# GPIO_Button_Grove_MOSFET_LED.net
KiCad netlist of a schematic drawn in EasyEDA Pro
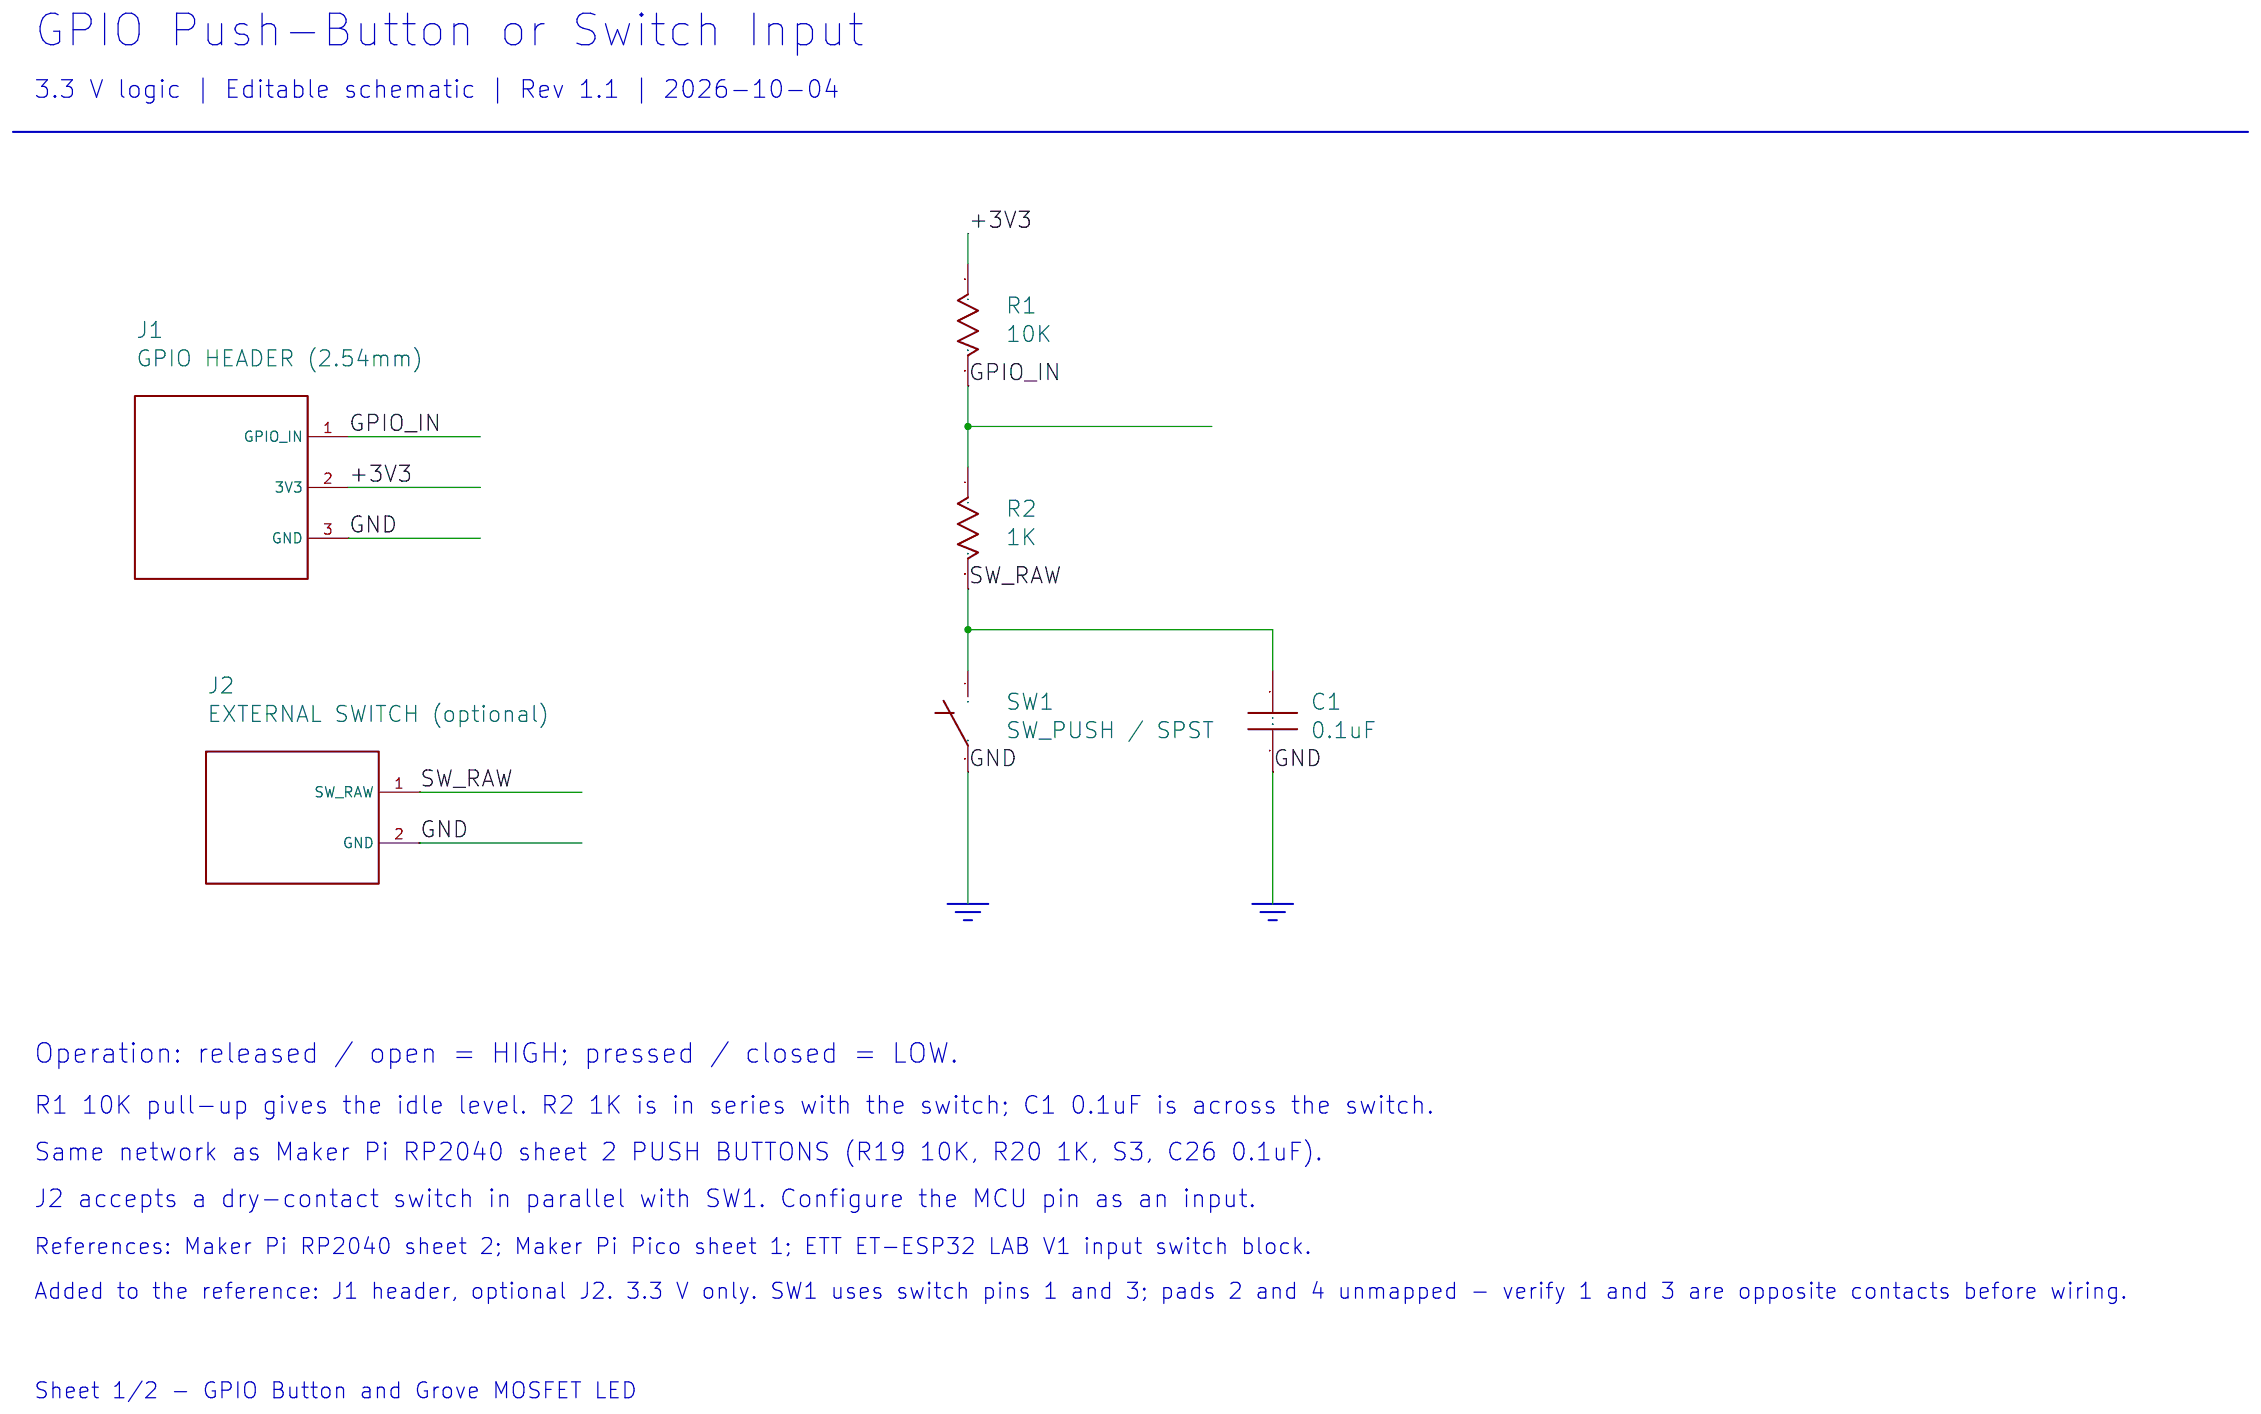
[diagram p0: GPIO_Push-Button_or_Switch_Input]
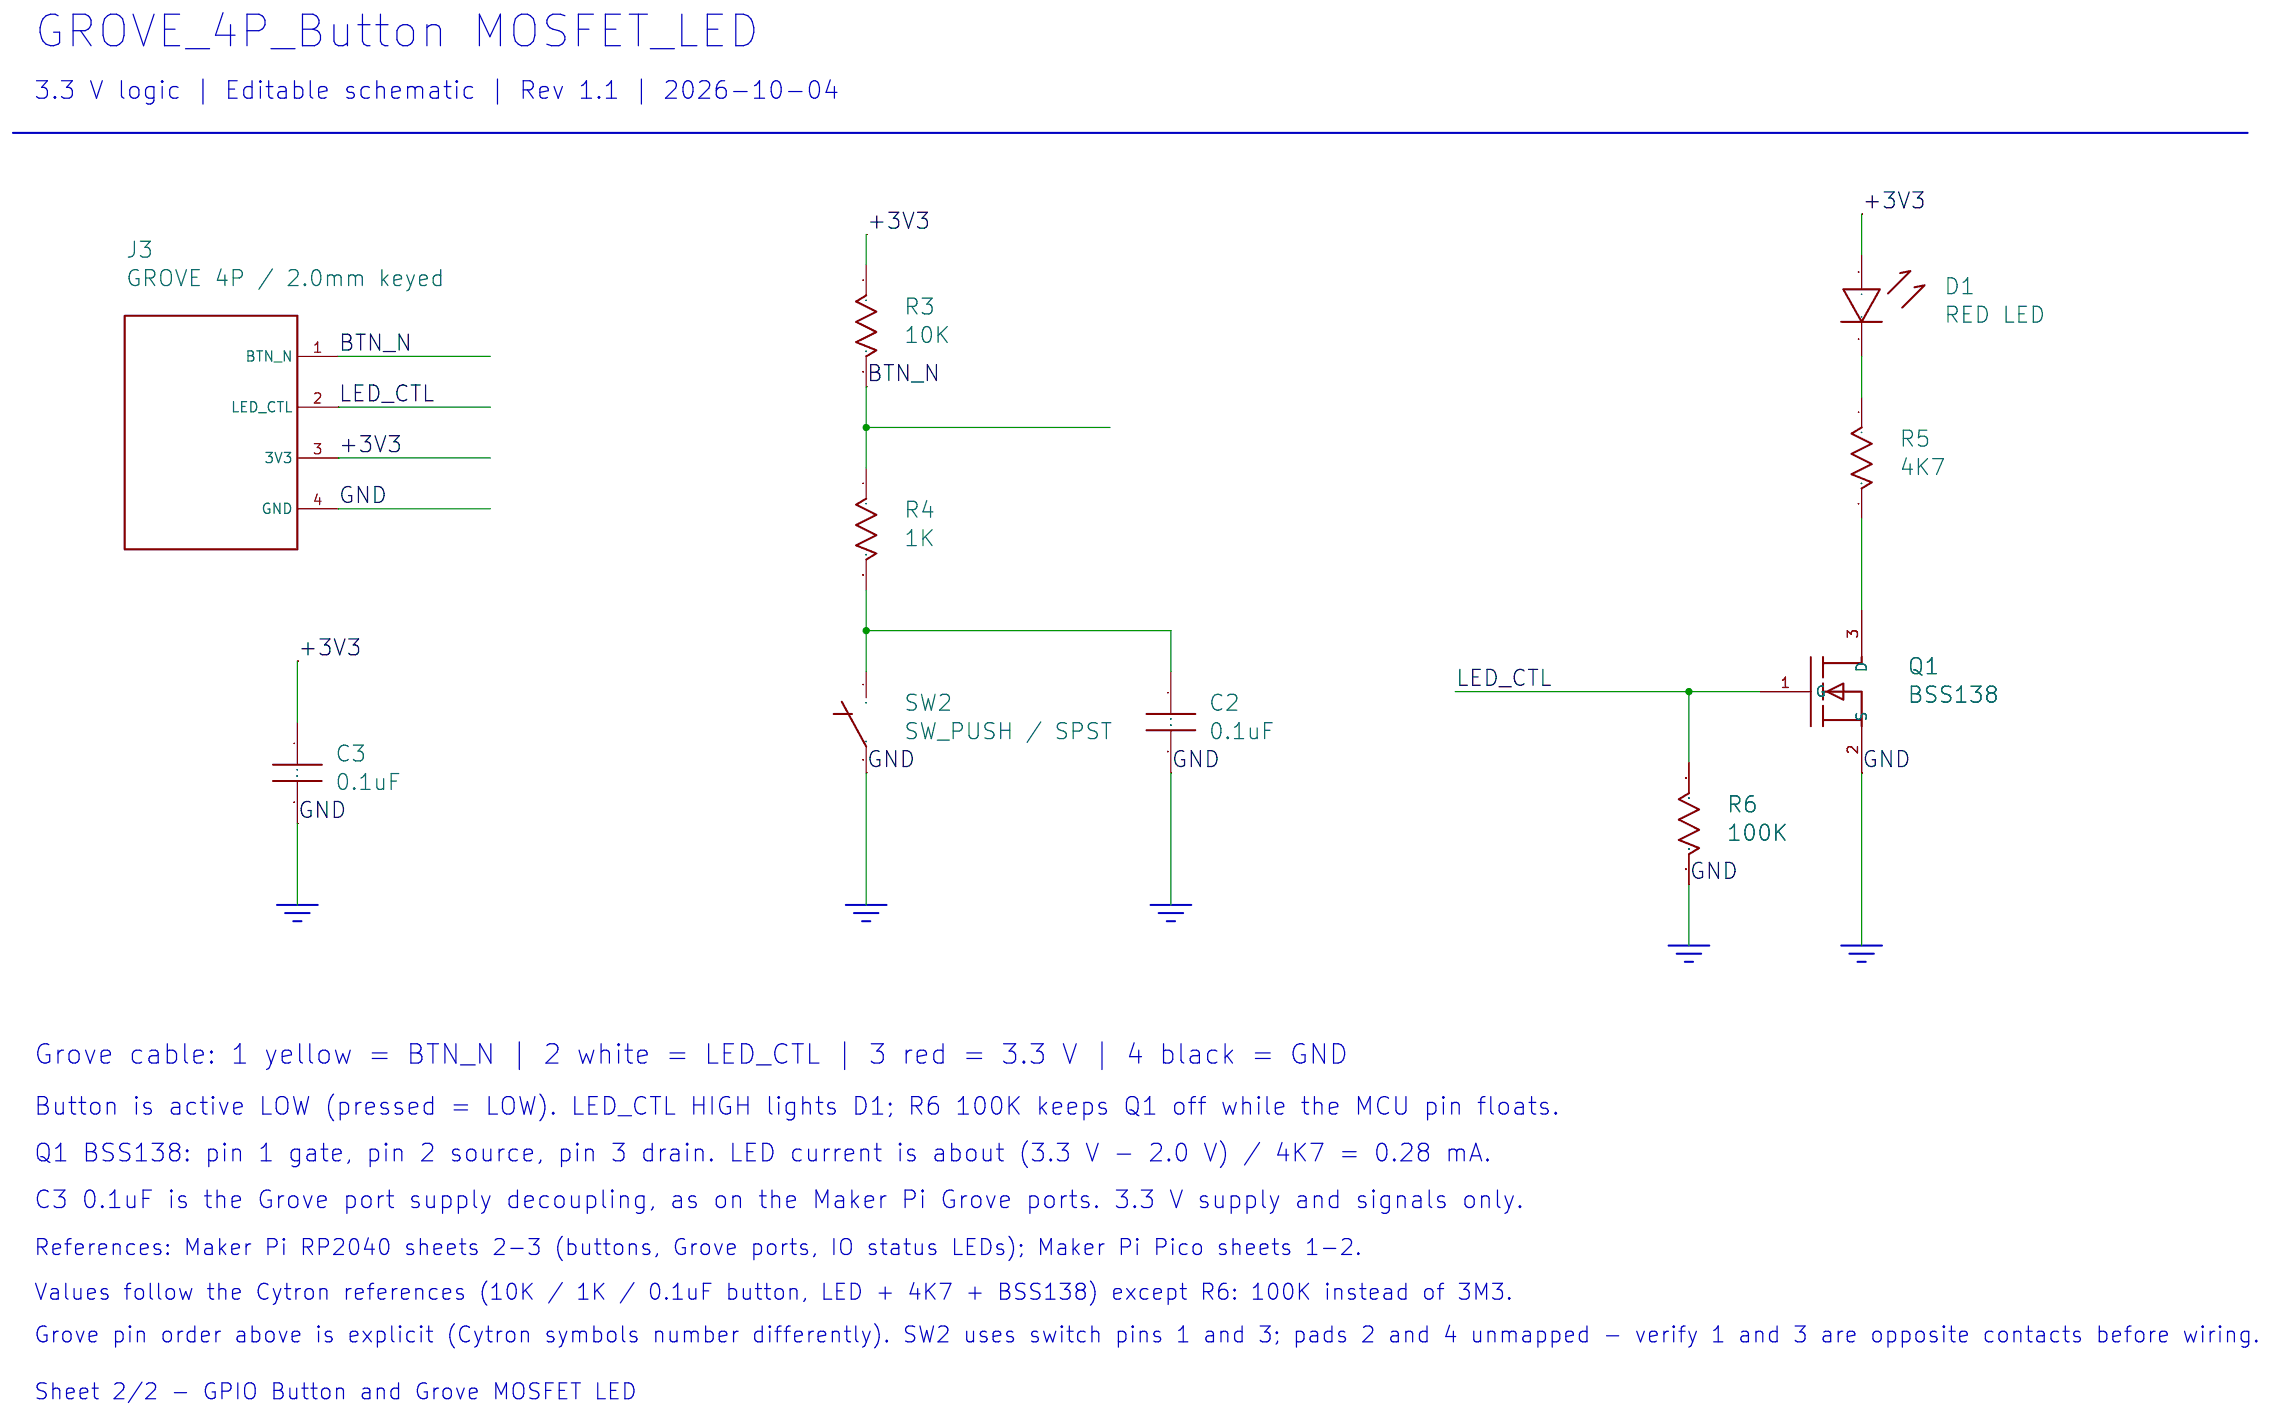
[diagram p1: GROVE_4P_Button_MOSFET_LED]

(export (version "E")
  (design (tool "Eeschema 10.0.6"))
  (components
    (comp (ref "C1")
      (value "0.1uF")
      (footprint "easyedapro:C0603")
      (libsource (lib "easyedapro") (part "0.1uF"))
    )
    (comp (ref "J1")
      (value "GPIO HEADER (2.54mm)")
      (libsource (lib "easyedapro") (part "GPIO HEADER (2.54mm)"))
    )
    (comp (ref "J2")
      (value "EXTERNAL SWITCH (optional)")
      (libsource (lib "easyedapro") (part "EXTERNAL SWITCH (optional)"))
    )
    (comp (ref "R1") (value "10K") (footprint "easyedapro:R0603") (libsource (lib "easyedapro") (part "10K")))
    (comp (ref "R2") (value "1K") (footprint "easyedapro:R0603") (libsource (lib "easyedapro") (part "1K")))
    (comp (ref "SW1") (value "SW_PUSH / SPST") (libsource (lib "easyedapro") (part "SW_PUSH / SPST")))
    (comp (ref "C2")
      (value "0.1uF")
      (footprint "easyedapro:C0603")
      (libsource (lib "easyedapro") (part "0.1uF"))
    )
    (comp (ref "C3")
      (value "0.1uF")
      (footprint "easyedapro:C0603")
      (libsource (lib "easyedapro") (part "0.1uF"))
    )
    (comp (ref "D1")
      (value "RED LED")
      (footprint "easyedapro:LED0603")
      (libsource (lib "easyedapro") (part "RED LED"))
    )
    (comp (ref "J3")
      (value "GROVE 4P / 2.0mm keyed")
      (libsource (lib "easyedapro") (part "GROVE 4P / 2.0mm keyed"))
    )
    (comp (ref "Q1") (value "BSS138") (libsource (lib "easyedapro") (part "BSS138")))
    (comp (ref "R3") (value "10K") (footprint "easyedapro:R0603") (libsource (lib "easyedapro") (part "10K")))
    (comp (ref "R4") (value "1K") (footprint "easyedapro:R0603") (libsource (lib "easyedapro") (part "1K")))
    (comp (ref "R5") (value "4K7") (footprint "easyedapro:R0603") (libsource (lib "easyedapro") (part "4K7")))
    (comp (ref "R6")
      (value "100K")
      (footprint "easyedapro:R0603")
      (libsource (lib "easyedapro") (part "3M3"))
    )
    (comp (ref "SW2") (value "SW_PUSH / SPST") (libsource (lib "easyedapro") (part "SW_PUSH / SPST")))
  )
  (nets
    (net (code "1") (name "+3V3") (class "Default")
      (node (ref "C3") (pin "1") (pinfunction "1_1") (pintype "unspecified"))
      (node (ref "D1") (pin "2") (pinfunction "A_2") (pintype "unspecified"))
      (node (ref "J1") (pin "2") (pinfunction "3V3_2") (pintype "unspecified"))
      (node (ref "J3") (pin "3") (pinfunction "3V3_3") (pintype "unspecified"))
      (node (ref "R1") (pin "1") (pinfunction "1_1") (pintype "unspecified"))
      (node (ref "R3") (pin "1") (pinfunction "1_1") (pintype "unspecified"))
    )
    (net (code "2") (name "BTN_N") (class "Default")
      (node (ref "J3") (pin "1") (pinfunction "BTN_N_1") (pintype "unspecified"))
      (node (ref "R3") (pin "2") (pinfunction "2_2") (pintype "unspecified"))
      (node (ref "R4") (pin "1") (pinfunction "1_1") (pintype "unspecified"))
    )
    (net (code "3") (name "GND") (class "Default")
      (node (ref "C1") (pin "2") (pinfunction "2_2") (pintype "unspecified"))
      (node (ref "C2") (pin "2") (pinfunction "2_2") (pintype "unspecified"))
      (node (ref "C3") (pin "2") (pinfunction "2_2") (pintype "unspecified"))
      (node (ref "J1") (pin "3") (pinfunction "GND_3") (pintype "unspecified"))
      (node (ref "J2") (pin "2") (pinfunction "GND_2") (pintype "unspecified"))
      (node (ref "J3") (pin "4") (pinfunction "GND_4") (pintype "unspecified"))
      (node (ref "Q1") (pin "2") (pinfunction "S_2") (pintype "unspecified"))
      (node (ref "R6") (pin "2") (pinfunction "2_2") (pintype "unspecified"))
      (node (ref "SW1") (pin "2") (pinfunction "2_2") (pintype "unspecified"))
      (node (ref "SW2") (pin "2") (pinfunction "2_2") (pintype "unspecified"))
    )
    (net (code "4") (name "GPIO_IN") (class "Default")
      (node (ref "J1") (pin "1") (pinfunction "GPIO_IN_1") (pintype "unspecified"))
      (node (ref "R1") (pin "2") (pinfunction "2_2") (pintype "unspecified"))
      (node (ref "R2") (pin "1") (pinfunction "1_1") (pintype "unspecified"))
    )
    (net (code "5") (name "LED_CTL") (class "Default")
      (node (ref "J3") (pin "2") (pinfunction "LED_CTL_2") (pintype "unspecified"))
      (node (ref "Q1") (pin "1") (pinfunction "G_1") (pintype "unspecified"))
      (node (ref "R6") (pin "1") (pinfunction "1_1") (pintype "unspecified"))
    )
    (net (code "6") (name "Net-(C2-Pad1)") (class "Default")
      (node (ref "C2") (pin "1") (pinfunction "1_1") (pintype "unspecified"))
      (node (ref "R4") (pin "2") (pinfunction "2_2") (pintype "unspecified"))
      (node (ref "SW2") (pin "1") (pinfunction "1_1") (pintype "unspecified"))
    )
    (net (code "7") (name "Net-(D1-K)") (class "Default")
      (node (ref "D1") (pin "1") (pinfunction "K_1") (pintype "unspecified"))
      (node (ref "R5") (pin "1") (pinfunction "1_1") (pintype "unspecified"))
    )
    (net (code "8") (name "Net-(Q1-D)") (class "Default")
      (node (ref "Q1") (pin "3") (pinfunction "D_3") (pintype "unspecified"))
      (node (ref "R5") (pin "2") (pinfunction "2_2") (pintype "unspecified"))
    )
    (net (code "9") (name "SW_RAW") (class "Default")
      (node (ref "C1") (pin "1") (pinfunction "1_1") (pintype "unspecified"))
      (node (ref "J2") (pin "1") (pinfunction "SW_RAW_1") (pintype "unspecified"))
      (node (ref "R2") (pin "2") (pinfunction "2_2") (pintype "unspecified"))
      (node (ref "SW1") (pin "1") (pinfunction "1_1") (pintype "unspecified"))
    )
  )
)
